# Steuerungsmodul.net
KiCad netlist of a schematic drawn in EAGLE
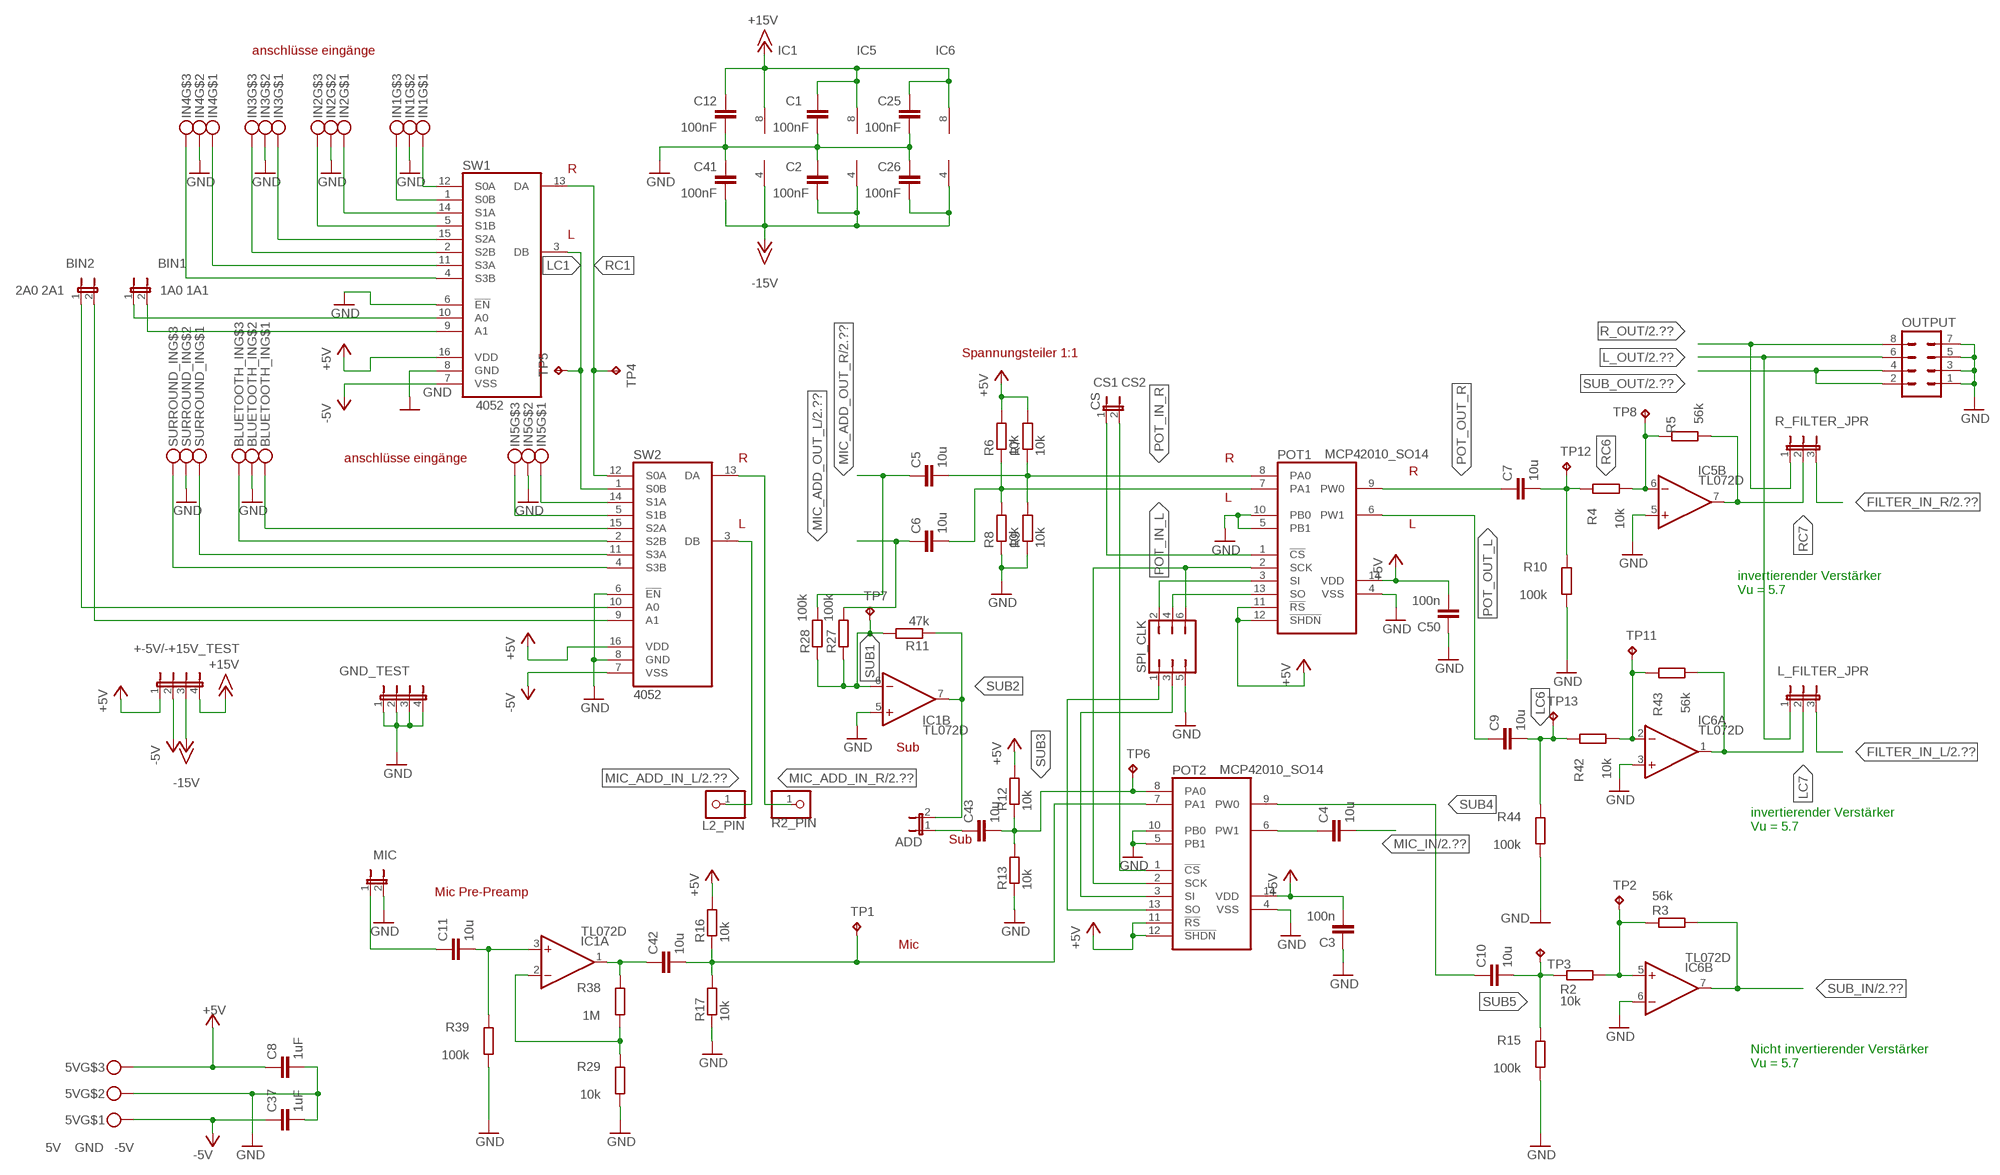
[diagram p0: schematic, sheet 1]
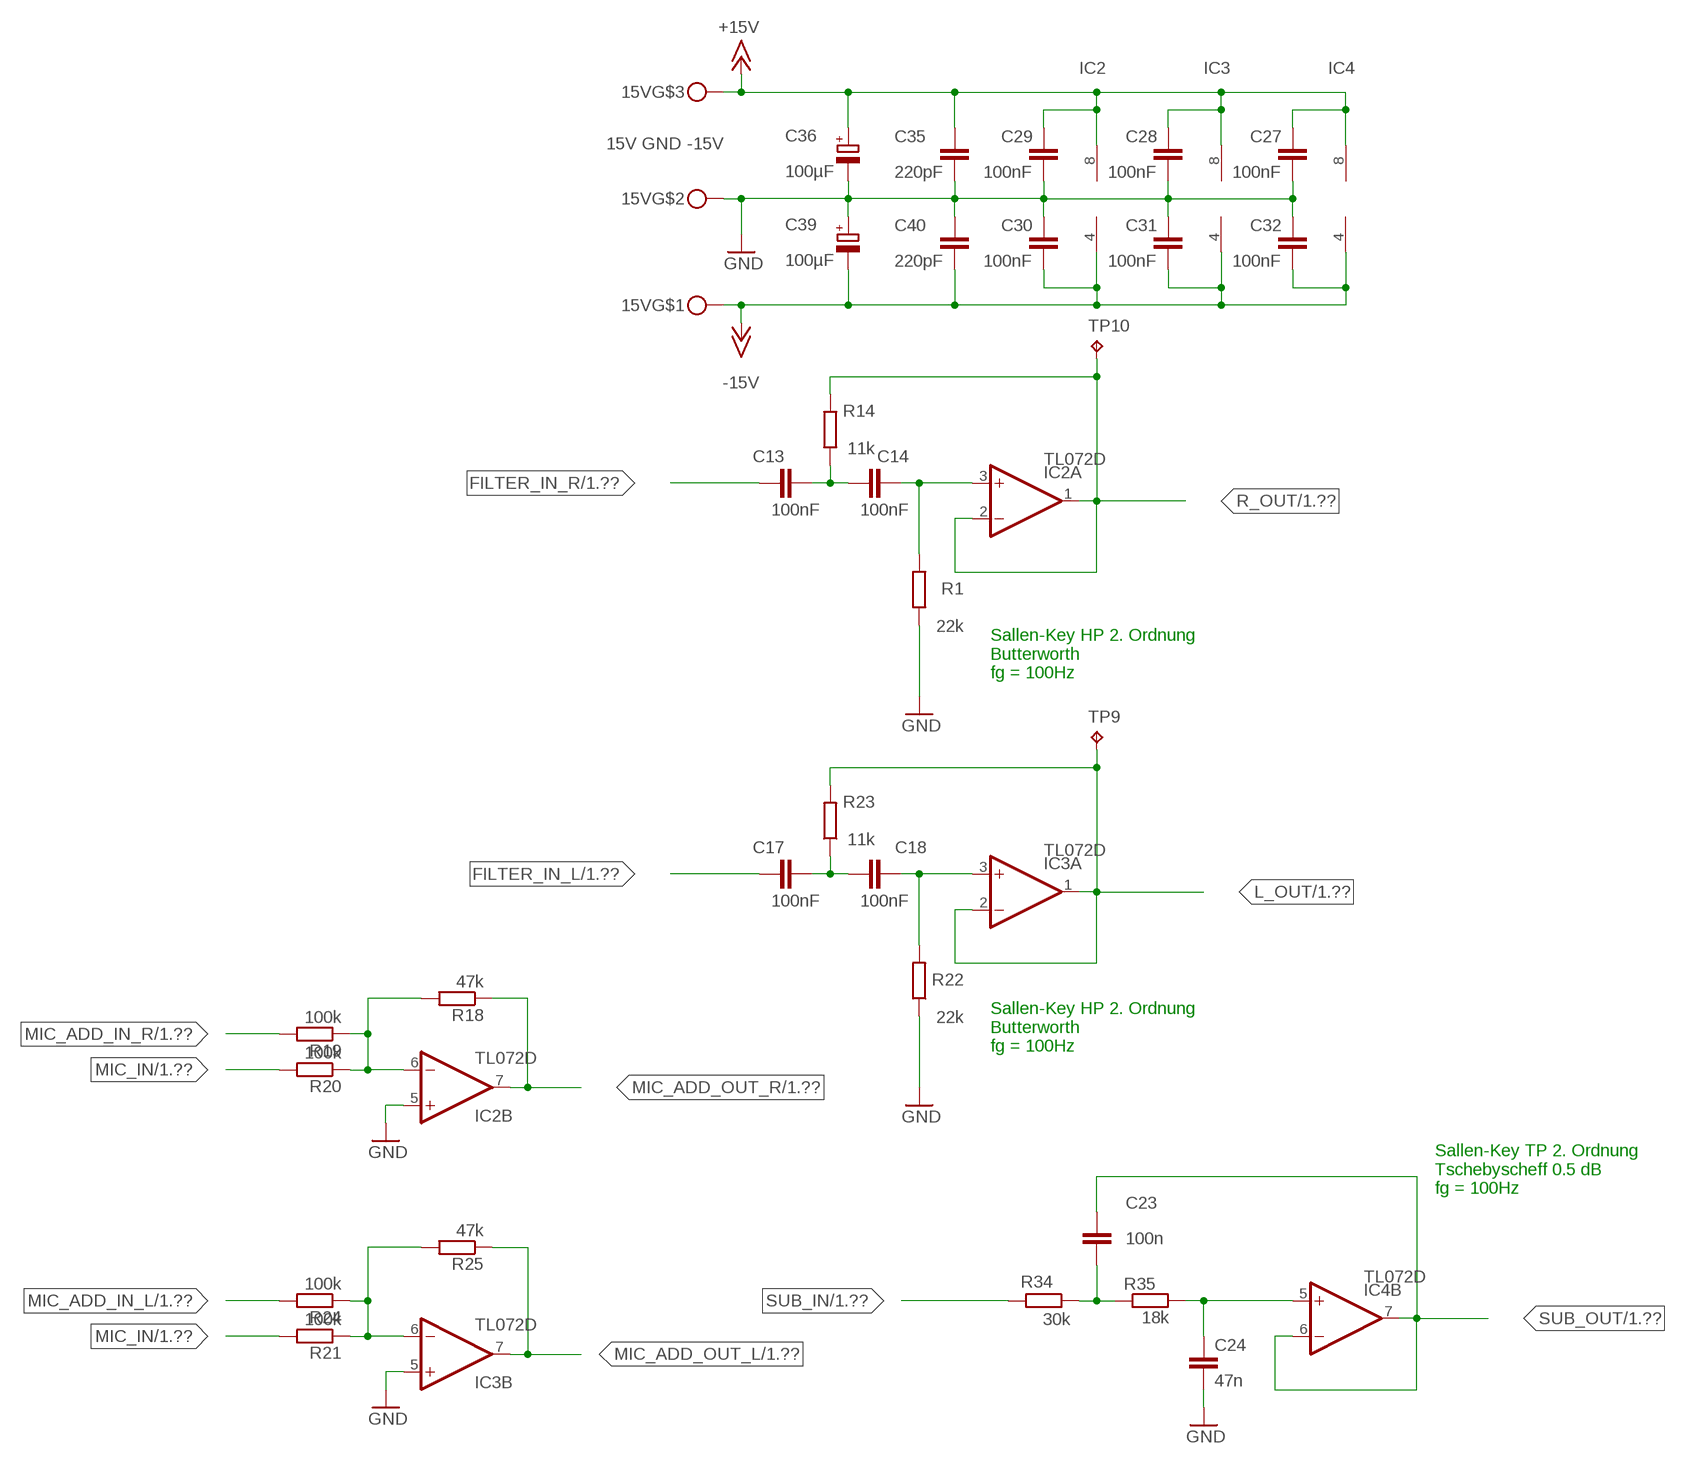
[diagram p1: schematic, sheet 2]

(export (version "E")
  (design (tool "Eeschema 10.0.6"))
  (components
    (comp (ref "+-5V/-+15V_TEST")
      (value "JP4E")
      (footprint "eagle-import:JP4")
      (libsource (lib "eagle-import") (part "JP4E"))
    )
    (comp (ref "5V")
      (value "5V GND -5V")
      (footprint "eagle-import:MKDS3_3_5,08")
      (libsource (lib "eagle-import") (part "MKDS3/3_5,08"))
    )
    (comp (ref "ADD")
      (value "JMP2")
      (footprint "eagle-import:JMP2")
      (libsource (lib "eagle-import") (part "JMP2"))
    )
    (comp (ref "BIN1")
      (value "1A0 1A1")
      (footprint "eagle-import:JMP2")
      (libsource (lib "eagle-import") (part "JMP2"))
    )
    (comp (ref "BIN2")
      (value "2A0 2A1")
      (footprint "eagle-import:JMP2")
      (fields (field (name "SPICEPREFIX") "B"))
      (libsource (lib "eagle-import") (part "JMP2"))
    )
    (comp (ref "BLUETOOTH_IN")
      (value "MKDS3/3_5,08")
      (footprint "eagle-import:MKDS3_3_5,08")
      (libsource (lib "eagle-import") (part "MKDS3/3_5,08"))
    )
    (comp (ref "C1")
      (value "100nF")
      (footprint "eagle-import:C0805")
      (libsource (lib "eagle-import") (part "C-EUC0805"))
    )
    (comp (ref "C2")
      (value "100nF")
      (footprint "eagle-import:C0805")
      (libsource (lib "eagle-import") (part "C-EUC0805"))
    )
    (comp (ref "C3")
      (value "100n")
      (footprint "eagle-import:C0805")
      (libsource (lib "eagle-import") (part "C-EUC0805"))
    )
    (comp (ref "C4")
      (value "10u")
      (footprint "eagle-import:C0805")
      (libsource (lib "eagle-import") (part "C-EUC0805"))
    )
    (comp (ref "C5")
      (value "10u")
      (footprint "eagle-import:C0805")
      (libsource (lib "eagle-import") (part "C-EUC0805"))
    )
    (comp (ref "C6")
      (value "10u")
      (footprint "eagle-import:C0805")
      (libsource (lib "eagle-import") (part "C-EUC0805"))
    )
    (comp (ref "C7")
      (value "10u")
      (footprint "eagle-import:C0805")
      (libsource (lib "eagle-import") (part "C-EUC0805"))
    )
    (comp (ref "C8")
      (value "1uF")
      (footprint "eagle-import:C0805")
      (libsource (lib "eagle-import") (part "C-EUC0805"))
    )
    (comp (ref "C9")
      (value "10u")
      (footprint "eagle-import:C0805")
      (libsource (lib "eagle-import") (part "C-EUC0805"))
    )
    (comp (ref "C10")
      (value "10u")
      (footprint "eagle-import:C0805")
      (libsource (lib "eagle-import") (part "C-EUC0805"))
    )
    (comp (ref "C11")
      (value "10u")
      (footprint "eagle-import:C0805")
      (libsource (lib "eagle-import") (part "C-EUC0805"))
    )
    (comp (ref "C12")
      (value "100nF")
      (footprint "eagle-import:C0805")
      (libsource (lib "eagle-import") (part "C-EUC0805"))
    )
    (comp (ref "C25")
      (value "100nF")
      (footprint "eagle-import:C0805")
      (libsource (lib "eagle-import") (part "C-EUC0805"))
    )
    (comp (ref "C26")
      (value "100nF")
      (footprint "eagle-import:C0805")
      (libsource (lib "eagle-import") (part "C-EUC0805"))
    )
    (comp (ref "C37")
      (value "1uF")
      (footprint "eagle-import:C0805")
      (libsource (lib "eagle-import") (part "C-EUC0805"))
    )
    (comp (ref "C41")
      (value "100nF")
      (footprint "eagle-import:C0805")
      (libsource (lib "eagle-import") (part "C-EUC0805"))
    )
    (comp (ref "C42")
      (value "10u")
      (footprint "eagle-import:C0805")
      (libsource (lib "eagle-import") (part "C-EUC0805"))
    )
    (comp (ref "C43")
      (value "10u")
      (footprint "eagle-import:C0805")
      (libsource (lib "eagle-import") (part "C-EUC0805"))
    )
    (comp (ref "C50")
      (value "100n")
      (footprint "eagle-import:C0805")
      (libsource (lib "eagle-import") (part "C-EUC0805"))
    )
    (comp (ref "CS")
      (value "CS1 CS2")
      (footprint "eagle-import:JMP2")
      (libsource (lib "eagle-import") (part "JMP2"))
    )
    (comp (ref "GND_TEST")
      (value "JP4E")
      (footprint "eagle-import:JP4")
      (libsource (lib "eagle-import") (part "jumper_252_JP4E"))
    )
    (comp (ref "IC1")
      (value "TL072D")
      (footprint "eagle-import:SO08")
      (libsource (lib "eagle-import") (part "TL072D"))
    )
    (comp (ref "IC5")
      (value "TL072D")
      (footprint "eagle-import:SO08")
      (libsource (lib "eagle-import") (part "TL072D"))
    )
    (comp (ref "IC6")
      (value "TL072D")
      (footprint "eagle-import:SO08")
      (libsource (lib "eagle-import") (part "TL072D"))
    )
    (comp (ref "IN1")
      (value "MKDS3/3_5,08")
      (footprint "eagle-import:MKDS3_3_5,08")
      (libsource (lib "eagle-import") (part "MKDS3/3_5,08"))
    )
    (comp (ref "IN2")
      (value "MKDS3/3_5,08")
      (footprint "eagle-import:MKDS3_3_5,08")
      (libsource (lib "eagle-import") (part "MKDS3/3_5,08"))
    )
    (comp (ref "IN3")
      (value "MKDS3/3_5,08")
      (footprint "eagle-import:MKDS3_3_5,08")
      (libsource (lib "eagle-import") (part "MKDS3/3_5,08"))
    )
    (comp (ref "IN4")
      (value "MKDS3/3_5,08")
      (footprint "eagle-import:MKDS3_3_5,08")
      (libsource (lib "eagle-import") (part "MKDS3/3_5,08"))
    )
    (comp (ref "IN5")
      (value "MKDS3/3_5,08")
      (footprint "eagle-import:MKDS3_3_5,08")
      (libsource (lib "eagle-import") (part "MKDS3/3_5,08"))
    )
    (comp (ref "L2_PIN")
      (value "PINHD-1X1")
      (footprint "eagle-import:1X01")
      (libsource (lib "eagle-import") (part "PINHD-1X1"))
    )
    (comp (ref "L_FILTER_JPR")
      (value "JMP3")
      (footprint "eagle-import:JMP3")
      (libsource (lib "eagle-import") (part "JMP3"))
    )
    (comp (ref "MIC")
      (value "JMP2")
      (footprint "eagle-import:JMP2")
      (libsource (lib "eagle-import") (part "JMP2"))
    )
    (comp (ref "OUTPUT")
      (value "MA04-2")
      (footprint "eagle-import:MA04-2")
      (libsource (lib "eagle-import") (part "MA04-2"))
    )
    (comp (ref "POT1")
      (value "MCP42010_SO14")
      (footprint "eagle-import:SO14")
      (libsource (lib "eagle-import") (part "MCP42010_SO14"))
    )
    (comp (ref "POT2")
      (value "MCP42010_SO14")
      (footprint "eagle-import:SO14")
      (libsource (lib "eagle-import") (part "MCP42010_SO14"))
    )
    (comp (ref "R2")
      (value "10k")
      (footprint "eagle-import:M0805")
      (libsource (lib "eagle-import") (part "R-EU_M0805"))
    )
    (comp (ref "R2_PIN")
      (value "PINHD-1X1")
      (footprint "eagle-import:1X01")
      (libsource (lib "eagle-import") (part "PINHD-1X1"))
    )
    (comp (ref "R3")
      (value "56k")
      (footprint "eagle-import:M0805")
      (libsource (lib "eagle-import") (part "R-EU_M0805"))
    )
    (comp (ref "R4")
      (value "10k")
      (footprint "eagle-import:M0805")
      (libsource (lib "eagle-import") (part "R-EU_M0805"))
    )
    (comp (ref "R5")
      (value "56k")
      (footprint "eagle-import:M0805")
      (libsource (lib "eagle-import") (part "R-EU_M0805"))
    )
    (comp (ref "R6")
      (value "10k")
      (footprint "eagle-import:M0805")
      (libsource (lib "eagle-import") (part "R-EU_M0805"))
    )
    (comp (ref "R7")
      (value "10k")
      (footprint "eagle-import:M0805")
      (libsource (lib "eagle-import") (part "R-EU_M0805"))
    )
    (comp (ref "R8")
      (value "10k")
      (footprint "eagle-import:M0805")
      (libsource (lib "eagle-import") (part "R-EU_M0805"))
    )
    (comp (ref "R9")
      (value "10k")
      (footprint "eagle-import:M0805")
      (libsource (lib "eagle-import") (part "R-EU_M0805"))
    )
    (comp (ref "R10")
      (value "100k")
      (footprint "eagle-import:M0805")
      (libsource (lib "eagle-import") (part "R-EU_M0805"))
    )
    (comp (ref "R11")
      (value "47k")
      (footprint "eagle-import:M0805")
      (libsource (lib "eagle-import") (part "R-EU_M0805"))
    )
    (comp (ref "R12")
      (value "10k")
      (footprint "eagle-import:M0805")
      (libsource (lib "eagle-import") (part "R-EU_M0805"))
    )
    (comp (ref "R13")
      (value "10k")
      (footprint "eagle-import:M0805")
      (libsource (lib "eagle-import") (part "R-EU_M0805"))
    )
    (comp (ref "R15")
      (value "100k")
      (footprint "eagle-import:M0805")
      (libsource (lib "eagle-import") (part "R-EU_M0805"))
    )
    (comp (ref "R16")
      (value "10k")
      (footprint "eagle-import:M0805")
      (libsource (lib "eagle-import") (part "R-EU_M0805"))
    )
    (comp (ref "R17")
      (value "10k")
      (footprint "eagle-import:M0805")
      (libsource (lib "eagle-import") (part "R-EU_M0805"))
    )
    (comp (ref "R27")
      (value "100k")
      (footprint "eagle-import:M0805")
      (libsource (lib "eagle-import") (part "R-EU_M0805"))
    )
    (comp (ref "R28")
      (value "100k")
      (footprint "eagle-import:M0805")
      (libsource (lib "eagle-import") (part "R-EU_M0805"))
    )
    (comp (ref "R29")
      (value "10k")
      (footprint "eagle-import:M0805")
      (libsource (lib "eagle-import") (part "R-EU_M0805"))
    )
    (comp (ref "R38")
      (value "1M")
      (footprint "eagle-import:M0805")
      (libsource (lib "eagle-import") (part "R-EU_M0805"))
    )
    (comp (ref "R39")
      (value "100k")
      (footprint "eagle-import:M0805")
      (libsource (lib "eagle-import") (part "R-EU_M0805"))
    )
    (comp (ref "R42")
      (value "10k")
      (footprint "eagle-import:M0805")
      (libsource (lib "eagle-import") (part "R-EU_M0805"))
    )
    (comp (ref "R43")
      (value "56k")
      (footprint "eagle-import:M0805")
      (libsource (lib "eagle-import") (part "R-EU_M0805"))
    )
    (comp (ref "R44")
      (value "100k")
      (footprint "eagle-import:M0805")
      (libsource (lib "eagle-import") (part "R-EU_M0805"))
    )
    (comp (ref "R_FILTER_JPR")
      (value "JMP3")
      (footprint "eagle-import:JMP3")
      (libsource (lib "eagle-import") (part "JMP3"))
    )
    (comp (ref "SPI_CLK")
      (value "JP3Q")
      (footprint "eagle-import:JP3Q")
      (libsource (lib "eagle-import") (part "JP3Q"))
    )
    (comp (ref "SURROUND_IN")
      (value "MKDS3/3_5,08")
      (footprint "eagle-import:MKDS3_3_5,08")
      (libsource (lib "eagle-import") (part "MKDS3/3_5,08"))
    )
    (comp (ref "SW1")
      (value "4052")
      (footprint "eagle-import:SO-16")
      (libsource (lib "eagle-import") (part "5042_SO16_NEU"))
    )
    (comp (ref "SW2")
      (value "4052")
      (footprint "eagle-import:SO-16")
      (libsource (lib "eagle-import") (part "5042_SO16_NEU"))
    )
    (comp (ref "TP1")
      (value "TPB2,54")
      (footprint "eagle-import:B2,54")
      (libsource (lib "eagle-import") (part "TPB2,54"))
    )
    (comp (ref "TP2")
      (value "TPB2,54")
      (footprint "eagle-import:B2,54")
      (libsource (lib "eagle-import") (part "TPB2,54"))
    )
    (comp (ref "TP3")
      (value "TPB2,54")
      (footprint "eagle-import:B2,54")
      (libsource (lib "eagle-import") (part "TPB2,54"))
    )
    (comp (ref "TP4")
      (value "TPB2,54")
      (footprint "eagle-import:B2,54")
      (libsource (lib "eagle-import") (part "TPB2,54"))
    )
    (comp (ref "TP5")
      (value "TPB2,54")
      (footprint "eagle-import:B2,54")
      (libsource (lib "eagle-import") (part "TPB2,54"))
    )
    (comp (ref "TP6")
      (value "TPB2,54")
      (footprint "eagle-import:B2,54")
      (libsource (lib "eagle-import") (part "TPB2,54"))
    )
    (comp (ref "TP7")
      (value "TPB2,54")
      (footprint "eagle-import:B2,54")
      (libsource (lib "eagle-import") (part "TPB2,54"))
    )
    (comp (ref "TP8")
      (value "TPB2,54")
      (footprint "eagle-import:B2,54")
      (libsource (lib "eagle-import") (part "TPB2,54"))
    )
    (comp (ref "TP11")
      (value "TPB2,54")
      (footprint "eagle-import:B2,54")
      (libsource (lib "eagle-import") (part "TPB2,54"))
    )
    (comp (ref "TP12")
      (value "TPB2,54")
      (footprint "eagle-import:B2,54")
      (libsource (lib "eagle-import") (part "TPB2,54"))
    )
    (comp (ref "TP13")
      (value "TPB2,54")
      (footprint "eagle-import:B2,54")
      (libsource (lib "eagle-import") (part "TPB2,54"))
    )
    (comp (ref "15V")
      (value "15V GND -15V")
      (footprint "eagle-import:MKDS3_3_5,08")
      (libsource (lib "eagle-import") (part "MKDS3/3_5,08"))
    )
    (comp (ref "C13")
      (value "100nF")
      (footprint "eagle-import:C0805")
      (libsource (lib "eagle-import") (part "C-EUC0805"))
    )
    (comp (ref "C14")
      (value "100nF")
      (footprint "eagle-import:C0805")
      (libsource (lib "eagle-import") (part "C-EUC0805"))
    )
    (comp (ref "C17")
      (value "100nF")
      (footprint "eagle-import:C0805")
      (libsource (lib "eagle-import") (part "C-EUC0805"))
    )
    (comp (ref "C18")
      (value "100nF")
      (footprint "eagle-import:C0805")
      (libsource (lib "eagle-import") (part "C-EUC0805"))
    )
    (comp (ref "C23")
      (value "100n")
      (footprint "eagle-import:C0805")
      (libsource (lib "eagle-import") (part "C-EUC0805"))
    )
    (comp (ref "C24")
      (value "47n")
      (footprint "eagle-import:C0805")
      (libsource (lib "eagle-import") (part "C-EUC0805"))
    )
    (comp (ref "C27")
      (value "100nF")
      (footprint "eagle-import:C0805")
      (libsource (lib "eagle-import") (part "C-EUC0805"))
    )
    (comp (ref "C28")
      (value "100nF")
      (footprint "eagle-import:C0805")
      (libsource (lib "eagle-import") (part "C-EUC0805"))
    )
    (comp (ref "C29")
      (value "100nF")
      (footprint "eagle-import:C0805")
      (libsource (lib "eagle-import") (part "C-EUC0805"))
    )
    (comp (ref "C30")
      (value "100nF")
      (footprint "eagle-import:C0805")
      (libsource (lib "eagle-import") (part "C-EUC0805"))
    )
    (comp (ref "C31")
      (value "100nF")
      (footprint "eagle-import:C0805")
      (libsource (lib "eagle-import") (part "C-EUC0805"))
    )
    (comp (ref "C32")
      (value "100nF")
      (footprint "eagle-import:C0805")
      (libsource (lib "eagle-import") (part "C-EUC0805"))
    )
    (comp (ref "C35")
      (value "220pF")
      (footprint "eagle-import:C0805")
      (libsource (lib "eagle-import") (part "C-EUC0805"))
    )
    (comp (ref "C36")
      (value "100µF")
      (footprint "eagle-import:E2,5-6")
      (libsource (lib "eagle-import") (part "CPOL-EUE2.5-6"))
    )
    (comp (ref "C39")
      (value "100µF")
      (footprint "eagle-import:E2,5-6")
      (libsource (lib "eagle-import") (part "CPOL-EUE2.5-6"))
    )
    (comp (ref "C40")
      (value "220pF")
      (footprint "eagle-import:C0805")
      (libsource (lib "eagle-import") (part "C-EUC0805"))
    )
    (comp (ref "IC2")
      (value "TL072D")
      (footprint "eagle-import:SO08")
      (libsource (lib "eagle-import") (part "TL072D"))
    )
    (comp (ref "IC3")
      (value "TL072D")
      (footprint "eagle-import:SO08")
      (libsource (lib "eagle-import") (part "TL072D"))
    )
    (comp (ref "IC4")
      (value "TL072D")
      (footprint "eagle-import:SO08")
      (libsource (lib "eagle-import") (part "TL072D"))
    )
    (comp (ref "R1")
      (value "22k")
      (footprint "eagle-import:M0805")
      (libsource (lib "eagle-import") (part "R-EU_M0805"))
    )
    (comp (ref "R14")
      (value "11k")
      (footprint "eagle-import:M0805")
      (libsource (lib "eagle-import") (part "R-EU_M0805"))
    )
    (comp (ref "R18")
      (value "47k")
      (footprint "eagle-import:M0805")
      (libsource (lib "eagle-import") (part "R-EU_M0805"))
    )
    (comp (ref "R19")
      (value "100k")
      (footprint "eagle-import:M0805")
      (libsource (lib "eagle-import") (part "R-EU_M0805"))
    )
    (comp (ref "R20")
      (value "100k")
      (footprint "eagle-import:M0805")
      (libsource (lib "eagle-import") (part "R-EU_M0805"))
    )
    (comp (ref "R21")
      (value "100k")
      (footprint "eagle-import:M0805")
      (libsource (lib "eagle-import") (part "R-EU_M0805"))
    )
    (comp (ref "R22")
      (value "22k")
      (footprint "eagle-import:M0805")
      (libsource (lib "eagle-import") (part "R-EU_M0805"))
    )
    (comp (ref "R23")
      (value "11k")
      (footprint "eagle-import:M0805")
      (libsource (lib "eagle-import") (part "R-EU_M0805"))
    )
    (comp (ref "R24")
      (value "100k")
      (footprint "eagle-import:M0805")
      (libsource (lib "eagle-import") (part "R-EU_M0805"))
    )
    (comp (ref "R25")
      (value "47k")
      (footprint "eagle-import:M0805")
      (libsource (lib "eagle-import") (part "R-EU_M0805"))
    )
    (comp (ref "R34")
      (value "30k")
      (footprint "eagle-import:M0805")
      (libsource (lib "eagle-import") (part "R-EU_M0805"))
    )
    (comp (ref "R35")
      (value "18k")
      (footprint "eagle-import:M0805")
      (libsource (lib "eagle-import") (part "R-EU_M0805"))
    )
    (comp (ref "TP9")
      (value "TPB2,54")
      (footprint "eagle-import:B2,54")
      (libsource (lib "eagle-import") (part "TPB2,54"))
    )
    (comp (ref "TP10")
      (value "TPB2,54")
      (footprint "eagle-import:B2,54")
      (libsource (lib "eagle-import") (part "TPB2,54"))
    )
  )
  (nets
    (net (code "1") (name "+5V") (class "Default")
      (node (ref "+-5V/-+15V_TEST") (pin "1") (pinfunction "1_1") (pintype "passive"))
      (node (ref "5V") (pin "P$3") (pinfunction "KL_P$3") (pintype "passive"))
      (node (ref "C3") (pin "2") (pinfunction "2_2") (pintype "passive"))
      (node (ref "C50") (pin "2") (pinfunction "2_2") (pintype "passive"))
      (node (ref "C8") (pin "1") (pinfunction "1_1") (pintype "passive"))
      (node (ref "POT1") (pin "11") (pinfunction "~{RS}_11") (pintype "bidirectional"))
      (node (ref "POT1") (pin "12") (pinfunction "~{SHDN}_12") (pintype "bidirectional"))
      (node (ref "POT1") (pin "14") (pinfunction "VDD_14") (pintype "input"))
      (node (ref "POT2") (pin "11") (pinfunction "~{RS}_11") (pintype "bidirectional"))
      (node (ref "POT2") (pin "12") (pinfunction "~{SHDN}_12") (pintype "bidirectional"))
      (node (ref "POT2") (pin "14") (pinfunction "VDD_14") (pintype "input"))
      (node (ref "R12") (pin "2") (pinfunction "2_2") (pintype "passive"))
      (node (ref "R16") (pin "2") (pinfunction "2_2") (pintype "passive"))
      (node (ref "R6") (pin "2") (pinfunction "2_2") (pintype "passive"))
      (node (ref "R7") (pin "2") (pinfunction "2_2") (pintype "passive"))
      (node (ref "SW1") (pin "16") (pinfunction "VDD_16") (pintype "bidirectional"))
      (node (ref "SW2") (pin "16") (pinfunction "VDD_16") (pintype "bidirectional"))
    )
    (net (code "2") (name "+15V") (class "Default")
      (node (ref "+-5V/-+15V_TEST") (pin "4") (pinfunction "4_4") (pintype "passive"))
      (node (ref "15V") (pin "P$3") (pinfunction "KL_P$3") (pintype "passive"))
      (node (ref "C1") (pin "1") (pinfunction "1_1") (pintype "passive"))
      (node (ref "C12") (pin "1") (pinfunction "1_1") (pintype "passive"))
      (node (ref "C25") (pin "1") (pinfunction "1_1") (pintype "passive"))
      (node (ref "C27") (pin "1") (pinfunction "1_1") (pintype "passive"))
      (node (ref "C28") (pin "1") (pinfunction "1_1") (pintype "passive"))
      (node (ref "C29") (pin "1") (pinfunction "1_1") (pintype "passive"))
      (node (ref "C35") (pin "1") (pinfunction "1_1") (pintype "passive"))
      (node (ref "C36") (pin "+") (pinfunction "+_+") (pintype "passive"))
      (node (ref "IC1") (pin "8") (pinfunction "V+_8") (pintype "power_in"))
      (node (ref "IC2") (pin "8") (pinfunction "V+_8") (pintype "power_in"))
      (node (ref "IC3") (pin "8") (pinfunction "V+_8") (pintype "power_in"))
      (node (ref "IC4") (pin "8") (pinfunction "V+_8") (pintype "power_in"))
      (node (ref "IC5") (pin "8") (pinfunction "V+_8") (pintype "power_in"))
      (node (ref "IC6") (pin "8") (pinfunction "V+_8") (pintype "power_in"))
    )
    (net (code "3") (name "-5V") (class "Default")
      (node (ref "+-5V/-+15V_TEST") (pin "2") (pinfunction "2_2") (pintype "passive"))
      (node (ref "5V") (pin "P$1") (pinfunction "KL_P$1") (pintype "passive"))
      (node (ref "C37") (pin "1") (pinfunction "1_1") (pintype "passive"))
      (node (ref "SW1") (pin "7") (pinfunction "VSS_7") (pintype "bidirectional"))
      (node (ref "SW2") (pin "7") (pinfunction "VSS_7") (pintype "bidirectional"))
    )
    (net (code "4") (name "-15V") (class "Default")
      (node (ref "+-5V/-+15V_TEST") (pin "3") (pinfunction "3_3") (pintype "passive"))
      (node (ref "15V") (pin "P$1") (pinfunction "KL_P$1") (pintype "passive"))
      (node (ref "C2") (pin "2") (pinfunction "2_2") (pintype "passive"))
      (node (ref "C26") (pin "2") (pinfunction "2_2") (pintype "passive"))
      (node (ref "C30") (pin "2") (pinfunction "2_2") (pintype "passive"))
      (node (ref "C31") (pin "2") (pinfunction "2_2") (pintype "passive"))
      (node (ref "C32") (pin "2") (pinfunction "2_2") (pintype "passive"))
      (node (ref "C39") (pin "-") (pinfunction "-_-") (pintype "passive"))
      (node (ref "C40") (pin "2") (pinfunction "2_2") (pintype "passive"))
      (node (ref "C41") (pin "2") (pinfunction "2_2") (pintype "passive"))
      (node (ref "IC1") (pin "4") (pinfunction "V-_4") (pintype "power_in"))
      (node (ref "IC2") (pin "4") (pinfunction "V-_4") (pintype "power_in"))
      (node (ref "IC3") (pin "4") (pinfunction "V-_4") (pintype "power_in"))
      (node (ref "IC4") (pin "4") (pinfunction "V-_4") (pintype "power_in"))
      (node (ref "IC5") (pin "4") (pinfunction "V-_4") (pintype "power_in"))
      (node (ref "IC6") (pin "4") (pinfunction "V-_4") (pintype "power_in"))
    )
    (net (code "5") (name "FILTER_IN_L") (class "Default")
      (node (ref "C17") (pin "1") (pinfunction "1_1") (pintype "passive"))
      (node (ref "L_FILTER_JPR") (pin "3") (pinfunction "3_3") (pintype "passive"))
    )
    (net (code "6") (name "FILTER_IN_R") (class "Default")
      (node (ref "C13") (pin "1") (pinfunction "1_1") (pintype "passive"))
      (node (ref "R_FILTER_JPR") (pin "3") (pinfunction "3_3") (pintype "passive"))
    )
    (net (code "7") (name "GND") (class "Default")
      (node (ref "15V") (pin "P$2") (pinfunction "KL_P$2") (pintype "passive"))
      (node (ref "5V") (pin "P$2") (pinfunction "KL_P$2") (pintype "passive"))
      (node (ref "BLUETOOTH_IN") (pin "P$2") (pinfunction "KL_P$2") (pintype "passive"))
      (node (ref "C1") (pin "2") (pinfunction "2_2") (pintype "passive"))
      (node (ref "C12") (pin "2") (pinfunction "2_2") (pintype "passive"))
      (node (ref "C2") (pin "1") (pinfunction "1_1") (pintype "passive"))
      (node (ref "C24") (pin "2") (pinfunction "2_2") (pintype "passive"))
      (node (ref "C25") (pin "2") (pinfunction "2_2") (pintype "passive"))
      (node (ref "C26") (pin "1") (pinfunction "1_1") (pintype "passive"))
      (node (ref "C27") (pin "2") (pinfunction "2_2") (pintype "passive"))
      (node (ref "C28") (pin "2") (pinfunction "2_2") (pintype "passive"))
      (node (ref "C29") (pin "2") (pinfunction "2_2") (pintype "passive"))
      (node (ref "C3") (pin "1") (pinfunction "1_1") (pintype "passive"))
      (node (ref "C30") (pin "1") (pinfunction "1_1") (pintype "passive"))
      (node (ref "C31") (pin "1") (pinfunction "1_1") (pintype "passive"))
      (node (ref "C32") (pin "1") (pinfunction "1_1") (pintype "passive"))
      (node (ref "C35") (pin "2") (pinfunction "2_2") (pintype "passive"))
      (node (ref "C36") (pin "-") (pinfunction "-_-") (pintype "passive"))
      (node (ref "C37") (pin "2") (pinfunction "2_2") (pintype "passive"))
      (node (ref "C39") (pin "+") (pinfunction "+_+") (pintype "passive"))
      (node (ref "C40") (pin "1") (pinfunction "1_1") (pintype "passive"))
      (node (ref "C41") (pin "1") (pinfunction "1_1") (pintype "passive"))
      (node (ref "C50") (pin "1") (pinfunction "1_1") (pintype "passive"))
      (node (ref "C8") (pin "2") (pinfunction "2_2") (pintype "passive"))
      (node (ref "GND_TEST") (pin "1") (pinfunction "1_1") (pintype "passive"))
      (node (ref "GND_TEST") (pin "2") (pinfunction "2_2") (pintype "passive"))
      (node (ref "GND_TEST") (pin "3") (pinfunction "3_3") (pintype "passive"))
      (node (ref "GND_TEST") (pin "4") (pinfunction "4_4") (pintype "passive"))
      (node (ref "IC1") (pin "5") (pinfunction "+IN_5") (pintype "input"))
      (node (ref "IC2") (pin "5") (pinfunction "+IN_5") (pintype "input"))
      (node (ref "IC3") (pin "5") (pinfunction "+IN_5") (pintype "input"))
      (node (ref "IC5") (pin "5") (pinfunction "+IN_5") (pintype "input"))
      (node (ref "IC6") (pin "3") (pinfunction "+IN_3") (pintype "input"))
      (node (ref "IC6") (pin "6") (pinfunction "-IN_6") (pintype "input"))
      (node (ref "IN1") (pin "P$2") (pinfunction "KL_P$2") (pintype "passive"))
      (node (ref "IN2") (pin "P$2") (pinfunction "KL_P$2") (pintype "passive"))
      (node (ref "IN3") (pin "P$2") (pinfunction "KL_P$2") (pintype "passive"))
      (node (ref "IN4") (pin "P$2") (pinfunction "KL_P$2") (pintype "passive"))
      (node (ref "IN5") (pin "P$2") (pinfunction "KL_P$2") (pintype "passive"))
      (node (ref "MIC") (pin "2") (pinfunction "2_2") (pintype "passive"))
      (node (ref "OUTPUT") (pin "1") (pinfunction "1_1") (pintype "passive"))
      (node (ref "OUTPUT") (pin "3") (pinfunction "3_3") (pintype "passive"))
      (node (ref "OUTPUT") (pin "5") (pinfunction "5_5") (pintype "passive"))
      (node (ref "OUTPUT") (pin "7") (pinfunction "7_7") (pintype "passive"))
      (node (ref "POT1") (pin "10") (pinfunction "PB0_10") (pintype "bidirectional"))
      (node (ref "POT1") (pin "4") (pinfunction "VSS_4") (pintype "input"))
      (node (ref "POT1") (pin "5") (pinfunction "PB1_5") (pintype "bidirectional"))
      (node (ref "POT2") (pin "10") (pinfunction "PB0_10") (pintype "bidirectional"))
      (node (ref "POT2") (pin "4") (pinfunction "VSS_4") (pintype "input"))
      (node (ref "POT2") (pin "5") (pinfunction "PB1_5") (pintype "bidirectional"))
      (node (ref "R1") (pin "1") (pinfunction "1_1") (pintype "passive"))
      (node (ref "R10") (pin "1") (pinfunction "1_1") (pintype "passive"))
      (node (ref "R13") (pin "1") (pinfunction "1_1") (pintype "passive"))
      (node (ref "R15") (pin "1") (pinfunction "1_1") (pintype "passive"))
      (node (ref "R17") (pin "1") (pinfunction "1_1") (pintype "passive"))
      (node (ref "R22") (pin "1") (pinfunction "1_1") (pintype "passive"))
      (node (ref "R29") (pin "1") (pinfunction "1_1") (pintype "passive"))
      (node (ref "R39") (pin "1") (pinfunction "1_1") (pintype "passive"))
      (node (ref "R44") (pin "1") (pinfunction "1_1") (pintype "passive"))
      (node (ref "R8") (pin "1") (pinfunction "1_1") (pintype "passive"))
      (node (ref "R9") (pin "1") (pinfunction "1_1") (pintype "passive"))
      (node (ref "SPI_CLK") (pin "5") (pinfunction "5_5") (pintype "passive"))
      (node (ref "SURROUND_IN") (pin "P$2") (pinfunction "KL_P$2") (pintype "passive"))
      (node (ref "SW1") (pin "6") (pinfunction "~{EN}_6") (pintype "input"))
      (node (ref "SW1") (pin "8") (pinfunction "GND_8") (pintype "bidirectional"))
      (node (ref "SW2") (pin "6") (pinfunction "~{EN}_6") (pintype "input"))
      (node (ref "SW2") (pin "8") (pinfunction "GND_8") (pintype "bidirectional"))
    )
    (net (code "8") (name "LC1") (class "Default")
      (node (ref "SW1") (pin "3") (pinfunction "DB_3") (pintype "bidirectional"))
      (node (ref "SW2") (pin "1") (pinfunction "S0B_1") (pintype "bidirectional"))
      (node (ref "TP5") (pin "TP") (pinfunction "TP_TP") (pintype "input"))
    )
    (net (code "9") (name "LC6") (class "Default")
      (node (ref "C9") (pin "2") (pinfunction "2_2") (pintype "passive"))
      (node (ref "R42") (pin "2") (pinfunction "2_2") (pintype "passive"))
      (node (ref "R44") (pin "2") (pinfunction "2_2") (pintype "passive"))
      (node (ref "TP13") (pin "TP") (pinfunction "TP_TP") (pintype "input"))
    )
    (net (code "10") (name "LC7") (class "Default")
      (node (ref "IC6") (pin "1") (pinfunction "OUT_1") (pintype "output"))
      (node (ref "L_FILTER_JPR") (pin "2") (pinfunction "2_2") (pintype "passive"))
      (node (ref "R43") (pin "1") (pinfunction "1_1") (pintype "passive"))
    )
    (net (code "11") (name "L_OUT") (class "Default")
      (node (ref "IC3") (pin "1") (pinfunction "OUT_1") (pintype "output"))
      (node (ref "IC3") (pin "2") (pinfunction "-IN_2") (pintype "input"))
      (node (ref "L_FILTER_JPR") (pin "1") (pinfunction "1_1") (pintype "passive"))
      (node (ref "OUTPUT") (pin "6") (pinfunction "6_6") (pintype "passive"))
      (node (ref "R23") (pin "2") (pinfunction "2_2") (pintype "passive"))
      (node (ref "TP9") (pin "TP") (pinfunction "TP_TP") (pintype "input"))
    )
    (net (code "12") (name "MIC_ADD_IN_L") (class "Default")
      (node (ref "L2_PIN") (pin "1") (pinfunction "1_1") (pintype "passive"))
      (node (ref "R24") (pin "2") (pinfunction "2_2") (pintype "passive"))
      (node (ref "SW2") (pin "3") (pinfunction "DB_3") (pintype "bidirectional"))
    )
    (net (code "13") (name "MIC_ADD_IN_R") (class "Default")
      (node (ref "R19") (pin "2") (pinfunction "2_2") (pintype "passive"))
      (node (ref "R2_PIN") (pin "1") (pinfunction "1_1") (pintype "passive"))
      (node (ref "SW2") (pin "13") (pinfunction "DA_13") (pintype "bidirectional"))
    )
    (net (code "14") (name "MIC_ADD_OUT_L") (class "Default")
      (node (ref "C6") (pin "1") (pinfunction "1_1") (pintype "passive"))
      (node (ref "IC3") (pin "7") (pinfunction "OUT_7") (pintype "output"))
      (node (ref "R25") (pin "1") (pinfunction "1_1") (pintype "passive"))
      (node (ref "R27") (pin "2") (pinfunction "2_2") (pintype "passive"))
    )
    (net (code "15") (name "MIC_ADD_OUT_R") (class "Default")
      (node (ref "C5") (pin "1") (pinfunction "1_1") (pintype "passive"))
      (node (ref "IC2") (pin "7") (pinfunction "OUT_7") (pintype "output"))
      (node (ref "R18") (pin "1") (pinfunction "1_1") (pintype "passive"))
      (node (ref "R28") (pin "2") (pinfunction "2_2") (pintype "passive"))
    )
    (net (code "16") (name "MIC_IN") (class "Default")
      (node (ref "C4") (pin "2") (pinfunction "2_2") (pintype "passive"))
      (node (ref "R20") (pin "2") (pinfunction "2_2") (pintype "passive"))
      (node (ref "R21") (pin "2") (pinfunction "2_2") (pintype "passive"))
    )
    (net (code "17") (name "Net-(ADD-Pad1)") (class "Default")
      (node (ref "ADD") (pin "1") (pinfunction "1_1") (pintype "passive"))
      (node (ref "C43") (pin "1") (pinfunction "1_1") (pintype "passive"))
    )
    (net (code "18") (name "Net-(BLUETOOTH_INA-KL)") (class "Default")
      (node (ref "BLUETOOTH_IN") (pin "P$1") (pinfunction "KL_P$1") (pintype "passive"))
      (node (ref "SW2") (pin "15") (pinfunction "S2A_15") (pintype "bidirectional"))
    )
    (net (code "19") (name "Net-(BLUETOOTH_INC-KL)") (class "Default")
      (node (ref "BLUETOOTH_IN") (pin "P$3") (pinfunction "KL_P$3") (pintype "passive"))
      (node (ref "SW2") (pin "2") (pinfunction "S2B_2") (pintype "bidirectional"))
    )
    (net (code "20") (name "Net-(C11-Pad1)") (class "Default")
      (node (ref "C11") (pin "1") (pinfunction "1_1") (pintype "passive"))
      (node (ref "MIC") (pin "1") (pinfunction "1_1") (pintype "passive"))
    )
    (net (code "21") (name "Net-(C13-Pad2)") (class "Default")
      (node (ref "C13") (pin "2") (pinfunction "2_2") (pintype "passive"))
      (node (ref "C14") (pin "1") (pinfunction "1_1") (pintype "passive"))
      (node (ref "R14") (pin "1") (pinfunction "1_1") (pintype "passive"))
    )
    (net (code "22") (name "Net-(C17-Pad2)") (class "Default")
      (node (ref "C17") (pin "2") (pinfunction "2_2") (pintype "passive"))
      (node (ref "C18") (pin "1") (pinfunction "1_1") (pintype "passive"))
      (node (ref "R23") (pin "1") (pinfunction "1_1") (pintype "passive"))
    )
    (net (code "23") (name "Net-(C23-Pad2)") (class "Default")
      (node (ref "C23") (pin "2") (pinfunction "2_2") (pintype "passive"))
      (node (ref "R34") (pin "1") (pinfunction "1_1") (pintype "passive"))
      (node (ref "R35") (pin "1") (pinfunction "1_1") (pintype "passive"))
    )
    (net (code "24") (name "Net-(IC1A-+IN)") (class "Default")
      (node (ref "C11") (pin "2") (pinfunction "2_2") (pintype "passive"))
      (node (ref "IC1") (pin "3") (pinfunction "+IN_3") (pintype "input"))
      (node (ref "R39") (pin "2") (pinfunction "2_2") (pintype "passive"))
    )
    (net (code "25") (name "Net-(IC1A--IN)") (class "Default")
      (node (ref "IC1") (pin "2") (pinfunction "-IN_2") (pintype "input"))
      (node (ref "R29") (pin "2") (pinfunction "2_2") (pintype "passive"))
      (node (ref "R38") (pin "1") (pinfunction "1_1") (pintype "passive"))
    )
    (net (code "26") (name "Net-(IC1A-OUT)") (class "Default")
      (node (ref "C42") (pin "1") (pinfunction "1_1") (pintype "passive"))
      (node (ref "IC1") (pin "1") (pinfunction "OUT_1") (pintype "output"))
      (node (ref "R38") (pin "2") (pinfunction "2_2") (pintype "passive"))
    )
    (net (code "27") (name "Net-(IC2A-+IN)") (class "Default")
      (node (ref "C14") (pin "2") (pinfunction "2_2") (pintype "passive"))
      (node (ref "IC2") (pin "3") (pinfunction "+IN_3") (pintype "input"))
      (node (ref "R1") (pin "2") (pinfunction "2_2") (pintype "passive"))
    )
    (net (code "28") (name "Net-(IC2B--IN)") (class "Default")
      (node (ref "IC2") (pin "6") (pinfunction "-IN_6") (pintype "input"))
      (node (ref "R18") (pin "2") (pinfunction "2_2") (pintype "passive"))
      (node (ref "R19") (pin "1") (pinfunction "1_1") (pintype "passive"))
      (node (ref "R20") (pin "1") (pinfunction "1_1") (pintype "passive"))
    )
    (net (code "29") (name "Net-(IC3A-+IN)") (class "Default")
      (node (ref "C18") (pin "2") (pinfunction "2_2") (pintype "passive"))
      (node (ref "IC3") (pin "3") (pinfunction "+IN_3") (pintype "input"))
      (node (ref "R22") (pin "2") (pinfunction "2_2") (pintype "passive"))
    )
    (net (code "30") (name "Net-(IC3B--IN)") (class "Default")
      (node (ref "IC3") (pin "6") (pinfunction "-IN_6") (pintype "input"))
      (node (ref "R21") (pin "1") (pinfunction "1_1") (pintype "passive"))
      (node (ref "R24") (pin "1") (pinfunction "1_1") (pintype "passive"))
      (node (ref "R25") (pin "2") (pinfunction "2_2") (pintype "passive"))
    )
    (net (code "31") (name "Net-(IC4B-+IN)") (class "Default")
      (node (ref "C24") (pin "1") (pinfunction "1_1") (pintype "passive"))
      (node (ref "IC4") (pin "5") (pinfunction "+IN_5") (pintype "input"))
      (node (ref "R35") (pin "2") (pinfunction "2_2") (pintype "passive"))
    )
    (net (code "32") (name "Net-(IC5B--IN)") (class "Default")
      (node (ref "IC5") (pin "6") (pinfunction "-IN_6") (pintype "input"))
      (node (ref "R4") (pin "1") (pinfunction "1_1") (pintype "passive"))
      (node (ref "R5") (pin "2") (pinfunction "2_2") (pintype "passive"))
      (node (ref "TP8") (pin "TP") (pinfunction "TP_TP") (pintype "input"))
    )
    (net (code "33") (name "Net-(IC6A--IN)") (class "Default")
      (node (ref "IC6") (pin "2") (pinfunction "-IN_2") (pintype "input"))
      (node (ref "R42") (pin "1") (pinfunction "1_1") (pintype "passive"))
      (node (ref "R43") (pin "2") (pinfunction "2_2") (pintype "passive"))
      (node (ref "TP11") (pin "TP") (pinfunction "TP_TP") (pintype "input"))
    )
    (net (code "34") (name "Net-(IC6B-+IN)") (class "Default")
      (node (ref "IC6") (pin "5") (pinfunction "+IN_5") (pintype "input"))
      (node (ref "R2") (pin "1") (pinfunction "1_1") (pintype "passive"))
      (node (ref "R3") (pin "2") (pinfunction "2_2") (pintype "passive"))
      (node (ref "TP2") (pin "TP") (pinfunction "TP_TP") (pintype "input"))
    )
    (net (code "35") (name "Net-(IN1A-KL)") (class "Default")
      (node (ref "IN1") (pin "P$1") (pinfunction "KL_P$1") (pintype "passive"))
      (node (ref "SW1") (pin "12") (pinfunction "S0A_12") (pintype "bidirectional"))
    )
    (net (code "36") (name "Net-(IN1C-KL)") (class "Default")
      (node (ref "IN1") (pin "P$3") (pinfunction "KL_P$3") (pintype "passive"))
      (node (ref "SW1") (pin "1") (pinfunction "S0B_1") (pintype "bidirectional"))
    )
    (net (code "37") (name "Net-(IN2A-KL)") (class "Default")
      (node (ref "IN2") (pin "P$1") (pinfunction "KL_P$1") (pintype "passive"))
      (node (ref "SW1") (pin "14") (pinfunction "S1A_14") (pintype "bidirectional"))
    )
    (net (code "38") (name "Net-(IN2C-KL)") (class "Default")
      (node (ref "IN2") (pin "P$3") (pinfunction "KL_P$3") (pintype "passive"))
      (node (ref "SW1") (pin "5") (pinfunction "S1B_5") (pintype "bidirectional"))
    )
    (net (code "39") (name "Net-(IN3A-KL)") (class "Default")
      (node (ref "IN3") (pin "P$1") (pinfunction "KL_P$1") (pintype "passive"))
      (node (ref "SW1") (pin "15") (pinfunction "S2A_15") (pintype "bidirectional"))
    )
    (net (code "40") (name "Net-(IN3C-KL)") (class "Default")
      (node (ref "IN3") (pin "P$3") (pinfunction "KL_P$3") (pintype "passive"))
      (node (ref "SW1") (pin "2") (pinfunction "S2B_2") (pintype "bidirectional"))
    )
    (net (code "41") (name "Net-(IN4A-KL)") (class "Default")
      (node (ref "IN4") (pin "P$1") (pinfunction "KL_P$1") (pintype "passive"))
      (node (ref "SW1") (pin "11") (pinfunction "S3A_11") (pintype "bidirectional"))
    )
    (net (code "42") (name "Net-(IN4C-KL)") (class "Default")
      (node (ref "IN4") (pin "P$3") (pinfunction "KL_P$3") (pintype "passive"))
      (node (ref "SW1") (pin "4") (pinfunction "S3B_4") (pintype "bidirectional"))
    )
    (net (code "43") (name "Net-(IN5A-KL)") (class "Default")
      (node (ref "IN5") (pin "P$1") (pinfunction "KL_P$1") (pintype "passive"))
      (node (ref "SW2") (pin "14") (pinfunction "S1A_14") (pintype "bidirectional"))
    )
    (net (code "44") (name "Net-(IN5C-KL)") (class "Default")
      (node (ref "IN5") (pin "P$3") (pinfunction "KL_P$3") (pintype "passive"))
      (node (ref "SW2") (pin "5") (pinfunction "S1B_5") (pintype "bidirectional"))
    )
    (net (code "45") (name "Net-(POT1-SCK)") (class "Default")
      (node (ref "POT1") (pin "2") (pinfunction "SCK_2") (pintype "bidirectional"))
      (node (ref "POT2") (pin "2") (pinfunction "SCK_2") (pintype "bidirectional"))
      (node (ref "SPI_CLK") (pin "6") (pinfunction "6_6") (pintype "passive"))
    )
    (net (code "46") (name "Net-(POT1-SI)") (class "Default")
      (node (ref "POT1") (pin "3") (pinfunction "SI_3") (pintype "bidirectional"))
      (node (ref "SPI_CLK") (pin "2") (pinfunction "2_2") (pintype "passive"))
    )
    (net (code "47") (name "Net-(POT1-SO)") (class "Default")
      (node (ref "POT1") (pin "13") (pinfunction "SO_13") (pintype "bidirectional"))
      (node (ref "SPI_CLK") (pin "4") (pinfunction "4_4") (pintype "passive"))
    )
    (net (code "48") (name "Net-(POT1-~{CS})") (class "Default")
      (node (ref "CS") (pin "1") (pinfunction "1_1") (pintype "passive"))
      (node (ref "POT1") (pin "1") (pinfunction "~{CS}_1") (pintype "bidirectional"))
    )
    (net (code "49") (name "Net-(POT2-PA1)") (class "Default")
      (node (ref "C42") (pin "2") (pinfunction "2_2") (pintype "passive"))
      (node (ref "POT2") (pin "7") (pinfunction "PA1_7") (pintype "bidirectional"))
      (node (ref "R16") (pin "1") (pinfunction "1_1") (pintype "passive"))
      (node (ref "R17") (pin "2") (pinfunction "2_2") (pintype "passive"))
      (node (ref "TP1") (pin "TP") (pinfunction "TP_TP") (pintype "input"))
    )
    (net (code "50") (name "Net-(POT2-PW1)") (class "Default")
      (node (ref "C4") (pin "1") (pinfunction "1_1") (pintype "passive"))
      (node (ref "POT2") (pin "6") (pinfunction "PW1_6") (pintype "bidirectional"))
    )
    (net (code "51") (name "Net-(POT2-SI)") (class "Default")
      (node (ref "POT2") (pin "3") (pinfunction "SI_3") (pintype "bidirectional"))
      (node (ref "SPI_CLK") (pin "3") (pinfunction "3_3") (pintype "passive"))
    )
    (net (code "52") (name "Net-(POT2-SO)") (class "Default")
      (node (ref "POT2") (pin "13") (pinfunction "SO_13") (pintype "bidirectional"))
      (node (ref "SPI_CLK") (pin "1") (pinfunction "1_1") (pintype "passive"))
    )
    (net (code "53") (name "Net-(POT2-~{CS})") (class "Default")
      (node (ref "CS") (pin "2") (pinfunction "2_2") (pintype "passive"))
      (node (ref "POT2") (pin "1") (pinfunction "~{CS}_1") (pintype "bidirectional"))
    )
    (net (code "54") (name "Net-(SURROUND_INA-KL)") (class "Default")
      (node (ref "SURROUND_IN") (pin "P$1") (pinfunction "KL_P$1") (pintype "passive"))
      (node (ref "SW2") (pin "11") (pinfunction "S3A_11") (pintype "bidirectional"))
    )
    (net (code "55") (name "Net-(SURROUND_INC-KL)") (class "Default")
      (node (ref "SURROUND_IN") (pin "P$3") (pinfunction "KL_P$3") (pintype "passive"))
      (node (ref "SW2") (pin "4") (pinfunction "S3B_4") (pintype "bidirectional"))
    )
    (net (code "56") (name "Net-(SW1-A0)") (class "Default")
      (node (ref "BIN1") (pin "1") (pinfunction "1_1") (pintype "passive"))
      (node (ref "SW1") (pin "10") (pinfunction "A0_10") (pintype "input"))
    )
    (net (code "57") (name "Net-(SW1-A1)") (class "Default")
      (node (ref "BIN1") (pin "2") (pinfunction "2_2") (pintype "passive"))
      (node (ref "SW1") (pin "9") (pinfunction "A1_9") (pintype "input"))
    )
    (net (code "58") (name "Net-(SW2-A0)") (class "Default")
      (node (ref "BIN2") (pin "1") (pinfunction "1_1") (pintype "passive"))
      (node (ref "SW2") (pin "10") (pinfunction "A0_10") (pintype "input"))
    )
    (net (code "59") (name "Net-(SW2-A1)") (class "Default")
      (node (ref "BIN2") (pin "2") (pinfunction "2_2") (pintype "passive"))
      (node (ref "SW2") (pin "9") (pinfunction "A1_9") (pintype "input"))
    )
    (net (code "60") (name "POT_IN_L") (class "Default")
      (node (ref "C6") (pin "2") (pinfunction "2_2") (pintype "passive"))
      (node (ref "POT1") (pin "7") (pinfunction "PA1_7") (pintype "bidirectional"))
      (node (ref "R6") (pin "1") (pinfunction "1_1") (pintype "passive"))
      (node (ref "R8") (pin "2") (pinfunction "2_2") (pintype "passive"))
    )
    (net (code "61") (name "POT_IN_R") (class "Default")
      (node (ref "C5") (pin "2") (pinfunction "2_2") (pintype "passive"))
      (node (ref "POT1") (pin "8") (pinfunction "PA0_8") (pintype "bidirectional"))
      (node (ref "R7") (pin "1") (pinfunction "1_1") (pintype "passive"))
      (node (ref "R9") (pin "2") (pinfunction "2_2") (pintype "passive"))
    )
    (net (code "62") (name "POT_OUT_L") (class "Default")
      (node (ref "C9") (pin "1") (pinfunction "1_1") (pintype "passive"))
      (node (ref "POT1") (pin "6") (pinfunction "PW1_6") (pintype "bidirectional"))
    )
    (net (code "63") (name "POT_OUT_R") (class "Default")
      (node (ref "C7") (pin "1") (pinfunction "1_1") (pintype "passive"))
      (node (ref "POT1") (pin "9") (pinfunction "PW0_9") (pintype "bidirectional"))
    )
    (net (code "64") (name "RC1") (class "Default")
      (node (ref "SW1") (pin "13") (pinfunction "DA_13") (pintype "bidirectional"))
      (node (ref "SW2") (pin "12") (pinfunction "S0A_12") (pintype "bidirectional"))
      (node (ref "TP4") (pin "TP") (pinfunction "TP_TP") (pintype "input"))
    )
    (net (code "65") (name "RC6") (class "Default")
      (node (ref "C7") (pin "2") (pinfunction "2_2") (pintype "passive"))
      (node (ref "R10") (pin "2") (pinfunction "2_2") (pintype "passive"))
      (node (ref "R4") (pin "2") (pinfunction "2_2") (pintype "passive"))
      (node (ref "TP12") (pin "TP") (pinfunction "TP_TP") (pintype "input"))
    )
    (net (code "66") (name "RC7") (class "Default")
      (node (ref "IC5") (pin "7") (pinfunction "OUT_7") (pintype "output"))
      (node (ref "R5") (pin "1") (pinfunction "1_1") (pintype "passive"))
      (node (ref "R_FILTER_JPR") (pin "2") (pinfunction "2_2") (pintype "passive"))
    )
    (net (code "67") (name "R_OUT") (class "Default")
      (node (ref "IC2") (pin "1") (pinfunction "OUT_1") (pintype "output"))
      (node (ref "IC2") (pin "2") (pinfunction "-IN_2") (pintype "input"))
      (node (ref "OUTPUT") (pin "8") (pinfunction "8_8") (pintype "passive"))
      (node (ref "R14") (pin "2") (pinfunction "2_2") (pintype "passive"))
      (node (ref "R_FILTER_JPR") (pin "1") (pinfunction "1_1") (pintype "passive"))
      (node (ref "TP10") (pin "TP") (pinfunction "TP_TP") (pintype "input"))
    )
    (net (code "68") (name "SUB1") (class "Default")
      (node (ref "IC1") (pin "6") (pinfunction "-IN_6") (pintype "input"))
      (node (ref "R11") (pin "2") (pinfunction "2_2") (pintype "passive"))
      (node (ref "R27") (pin "1") (pinfunction "1_1") (pintype "passive"))
      (node (ref "R28") (pin "1") (pinfunction "1_1") (pintype "passive"))
      (node (ref "TP7") (pin "TP") (pinfunction "TP_TP") (pintype "input"))
    )
    (net (code "69") (name "SUB2") (class "Default")
      (node (ref "ADD") (pin "2") (pinfunction "2_2") (pintype "passive"))
      (node (ref "IC1") (pin "7") (pinfunction "OUT_7") (pintype "output"))
      (node (ref "R11") (pin "1") (pinfunction "1_1") (pintype "passive"))
    )
    (net (code "70") (name "SUB3") (class "Default")
      (node (ref "C43") (pin "2") (pinfunction "2_2") (pintype "passive"))
      (node (ref "POT2") (pin "8") (pinfunction "PA0_8") (pintype "bidirectional"))
      (node (ref "R12") (pin "1") (pinfunction "1_1") (pintype "passive"))
      (node (ref "R13") (pin "2") (pinfunction "2_2") (pintype "passive"))
      (node (ref "TP6") (pin "TP") (pinfunction "TP_TP") (pintype "input"))
    )
    (net (code "71") (name "SUB4") (class "Default")
      (node (ref "C10") (pin "1") (pinfunction "1_1") (pintype "passive"))
      (node (ref "POT2") (pin "9") (pinfunction "PW0_9") (pintype "bidirectional"))
    )
    (net (code "72") (name "SUB5") (class "Default")
      (node (ref "C10") (pin "2") (pinfunction "2_2") (pintype "passive"))
      (node (ref "R15") (pin "2") (pinfunction "2_2") (pintype "passive"))
      (node (ref "R2") (pin "2") (pinfunction "2_2") (pintype "passive"))
      (node (ref "TP3") (pin "TP") (pinfunction "TP_TP") (pintype "input"))
    )
    (net (code "73") (name "SUB_IN") (class "Default")
      (node (ref "IC6") (pin "7") (pinfunction "OUT_7") (pintype "output"))
      (node (ref "R3") (pin "1") (pinfunction "1_1") (pintype "passive"))
      (node (ref "R34") (pin "2") (pinfunction "2_2") (pintype "passive"))
    )
    (net (code "74") (name "SUB_OUT") (class "Default")
      (node (ref "C23") (pin "1") (pinfunction "1_1") (pintype "passive"))
      (node (ref "IC4") (pin "6") (pinfunction "-IN_6") (pintype "input"))
      (node (ref "IC4") (pin "7") (pinfunction "OUT_7") (pintype "output"))
      (node (ref "OUTPUT") (pin "2") (pinfunction "2_2") (pintype "passive"))
      (node (ref "OUTPUT") (pin "4") (pinfunction "4_4") (pintype "passive"))
    )
  )
)
